# STM32F4_OSD_V12.net
KiCad netlist of a schematic drawn in Altium Designer
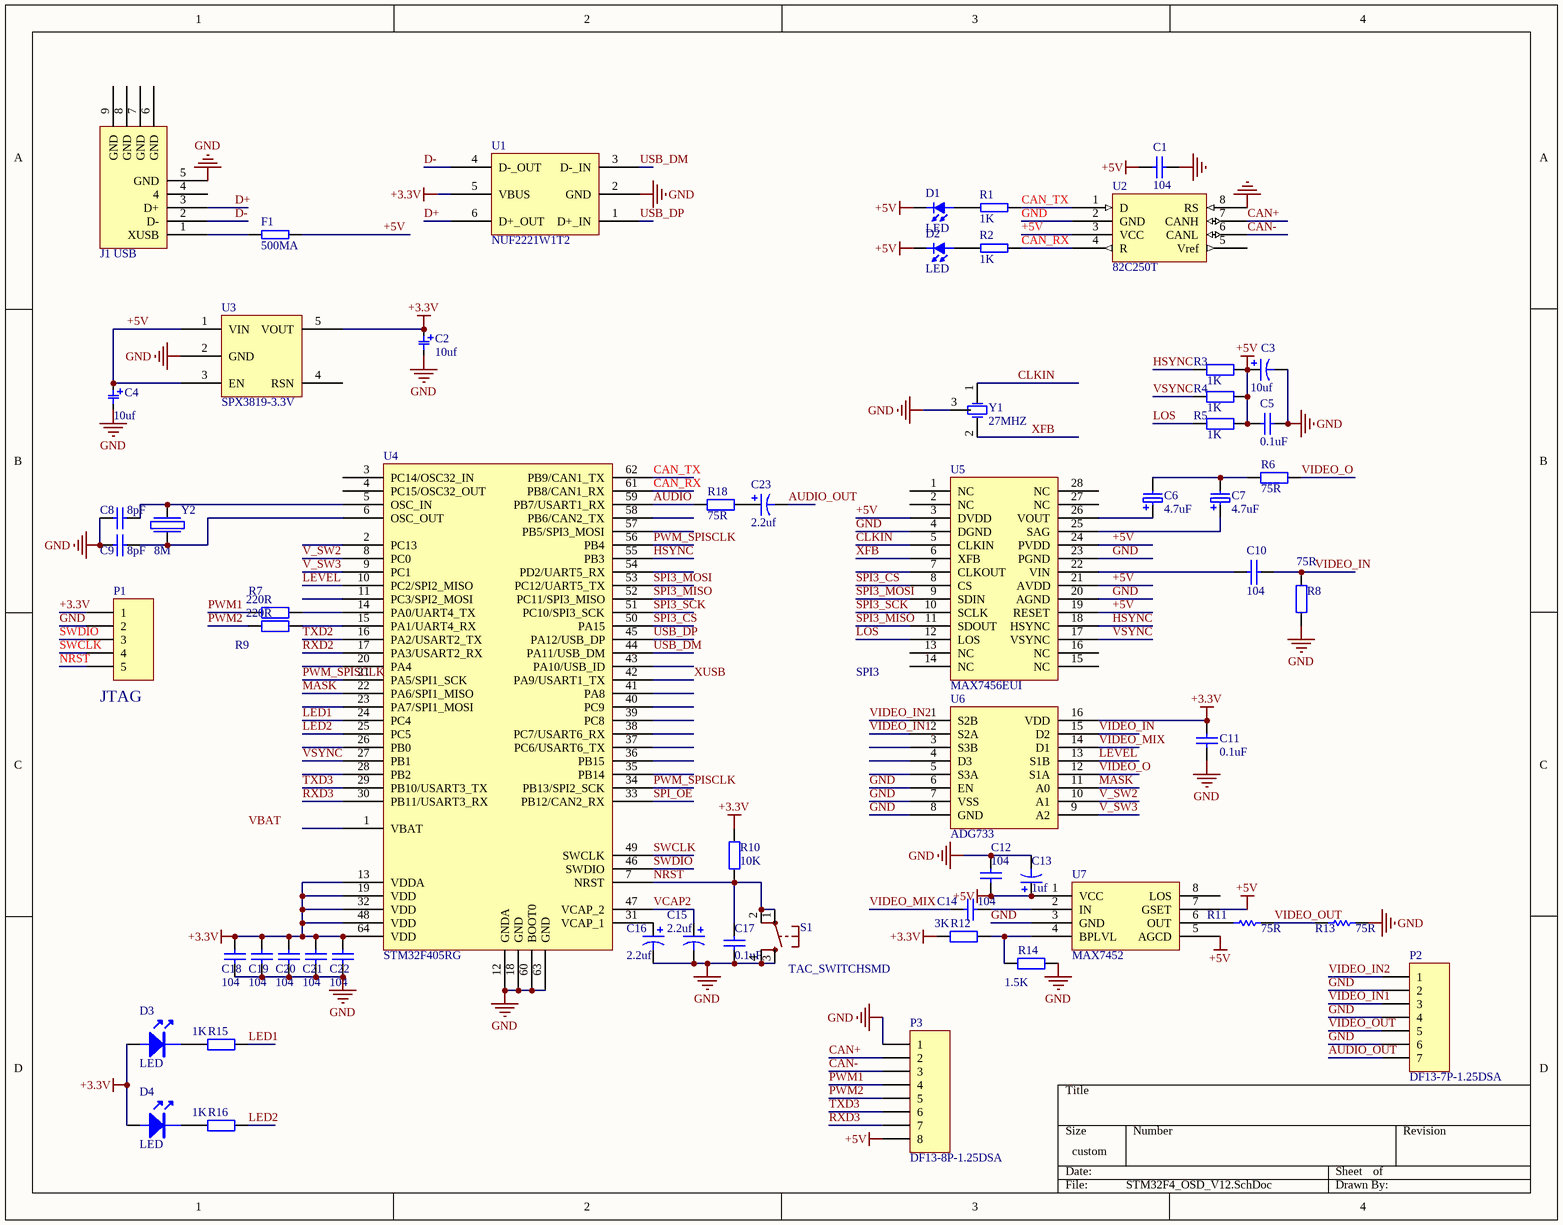
[diagram p0: STM32F4_OSD_V12.SchDoc]

(export (version "E")
  (design (tool "Eeschema 10.0.6"))
  (components
    (comp (ref "C1")
      (value "104")
      (footprint "0603C")
      (description "Capacitor")
      (fields (field (name "PUBLISHER") "Altium Limited"))
      (libsource (lib "*") (part "CAP"))
    )
    (comp (ref "C2") (value "10uf") (footprint "0805") (libsource (lib "电阻电容") (part "ECAP")))
    (comp (ref "C3")
      (value "10uf")
      (footprint "0603C")
      (description "Polarized Capacitor (Radial)")
      (libsource (lib "Miscellaneous Devices") (part "Cap Pol1"))
    )
    (comp (ref "C4") (value "10uf") (footprint "0805") (libsource (lib "电阻电容") (part "ECAP")))
    (comp (ref "C5")
      (value "0.1uF")
      (footprint "0402-CAP")
      (description "Capacitor")
      (fields (field (name "Comment") "Cap") (field (name "PUBLISHER") "Altium Limited"))
      (libsource (lib "Miscellaneous Devices") (part "Cap"))
    )
    (comp (ref "C6")
      (value "4.7uF")
      (footprint "0603C")
      (description "Electrolytic Capacitor 1")
      (libsource (lib "QT_SCH_V2") (part "ELECTRO1"))
    )
    (comp (ref "C7")
      (value "4.7uF")
      (footprint "0603C")
      (description "Electrolytic Capacitor 1")
      (libsource (lib "QT_SCH_V2") (part "ELECTRO1"))
    )
    (comp (ref "C8")
      (value "8pF")
      (footprint "0402-CAP")
      (description "Capacitor")
      (libsource (lib "EMotus Components") (part "CAP0805"))
    )
    (comp (ref "C9")
      (value "8pF")
      (footprint "0402-CAP")
      (description "Capacitor")
      (libsource (lib "EMotus Components") (part "CAP0805"))
    )
    (comp (ref "C10")
      (value "104")
      (footprint "0402-CAP")
      (description "Capacitor")
      (libsource (lib "") (part "CAP_1"))
    )
    (comp (ref "C11")
      (value "0.1uF")
      (footprint "0402-CAP")
      (description "Capacitor")
      (fields (field (name "Comment") "Cap") (field (name "PUBLISHER") "Altium Limited"))
      (libsource (lib "Miscellaneous Devices") (part "Cap"))
    )
    (comp (ref "C12")
      (value "104")
      (footprint "0402-CAP")
      (description "Capacitor")
      (libsource (lib "Miscellaneous Devices") (part "Cap"))
    )
    (comp (ref "C13")
      (value "1uf")
      (footprint "0603C")
      (description "Polarized Capacitor (Radial)")
      (libsource (lib "Miscellaneous Devices") (part "Cap Pol1"))
    )
    (comp (ref "C14")
      (value "104")
      (footprint "0402-CAP")
      (description "Capacitor")
      (libsource (lib "Miscellaneous Devices") (part "Cap"))
    )
    (comp (ref "C15")
      (value "2.2uf")
      (footprint "0603C")
      (description "Polarized Capacitor (Radial)")
      (libsource (lib "Miscellaneous Devices") (part "Cap Pol1"))
    )
    (comp (ref "C16")
      (value "2.2uf")
      (footprint "0603C")
      (description "Polarized Capacitor (Radial)")
      (libsource (lib "Miscellaneous Devices") (part "Cap Pol1"))
    )
    (comp (ref "C17")
      (value "0.1uF")
      (footprint "0402-CAP")
      (description "Capacitor")
      (fields (field (name "Comment") "Cap") (field (name "PUBLISHER") "Altium Limited"))
      (libsource (lib "Miscellaneous Devices") (part "Cap"))
    )
    (comp (ref "C18")
      (value "104")
      (footprint "0402-CAP")
      (description "Capacitor")
      (libsource (lib "Miscellaneous Devices") (part "Cap"))
    )
    (comp (ref "C19")
      (value "104")
      (footprint "0402-CAP")
      (description "Capacitor")
      (libsource (lib "Miscellaneous Devices") (part "Cap"))
    )
    (comp (ref "C20")
      (value "104")
      (footprint "0402-CAP")
      (description "Capacitor")
      (libsource (lib "Miscellaneous Devices") (part "Cap"))
    )
    (comp (ref "C21")
      (value "104")
      (footprint "0402-CAP")
      (description "Capacitor")
      (libsource (lib "Miscellaneous Devices") (part "Cap"))
    )
    (comp (ref "C22")
      (value "104")
      (footprint "0402-CAP")
      (description "Capacitor")
      (libsource (lib "Miscellaneous Devices") (part "Cap"))
    )
    (comp (ref "C23")
      (value "2.2uf")
      (footprint "0603C")
      (description "Polarized Capacitor (Radial)")
      (libsource (lib "Miscellaneous Devices") (part "Cap Pol1"))
    )
    (comp (ref "D1") (value "LED") (footprint "0603-LED") (libsource (lib "原理图库") (part "LED")))
    (comp (ref "D2") (value "LED") (footprint "0603-LED") (libsource (lib "原理图库") (part "LED")))
    (comp (ref "D3") (value "LED") (footprint "0603-LED") (libsource (lib "MySch") (part "LED")))
    (comp (ref "D4") (value "LED") (footprint "0603-LED") (libsource (lib "MySch") (part "LED")))
    (comp (ref "F1") (value "500MA") (footprint "PTC-1206") (libsource (lib "DXP常用原理图库.libsch") (part "RES")))
    (comp (ref "J1")
      (value "USB")
      (footprint "MOLEX_MICRO_USB_AB_BOTTOM_MOUNT")
      (libsource (lib "Schlib1") (part "USB"))
    )
    (comp (ref "P1")
      (value "JTAG")
      (footprint "DF13-5P-1.25DSA")
      (description "Header, 5-Pin")
      (libsource (lib "Miscellaneous Connectors") (part "Header 5"))
    )
    (comp (ref "P2")
      (value "DF13-7P-1.25DSA")
      (footprint "DF13C-7P-1.25V")
      (description "Header, 7-Pin")
      (libsource (lib "Miscellaneous Connectors") (part "Header 7"))
    )
    (comp (ref "P3")
      (value "DF13-8P-1.25DSA")
      (footprint "DF13C-8P-1.25V")
      (description "Header, 8-Pin")
      (libsource (lib "Miscellaneous Connectors") (part "Header 8"))
    )
    (comp (ref "R1") (value "1K") (footprint "0402-RES") (libsource (lib "DXP常用原理图库.libsch") (part "RES")))
    (comp (ref "R2") (value "1K") (footprint "0402-RES") (libsource (lib "DXP常用原理图库.libsch") (part "RES")))
    (comp (ref "R3")
      (value "1K")
      (footprint "0402-RES")
      (description "Resistor")
      (libsource (lib "") (part "Res2_1"))
    )
    (comp (ref "R4")
      (value "1K")
      (footprint "0402-RES")
      (description "Resistor")
      (libsource (lib "") (part "Res2_1"))
    )
    (comp (ref "R5")
      (value "1K")
      (footprint "0402-RES")
      (description "Resistor")
      (libsource (lib "") (part "Res2_1"))
    )
    (comp (ref "R6")
      (value "75R")
      (footprint "0402-RES")
      (description "Resistor")
      (libsource (lib "") (part "Res2_1"))
    )
    (comp (ref "R7")
      (value "220R")
      (footprint "0402-RES")
      (description "Resistor")
      (libsource (lib "") (part "Res2_2"))
    )
    (comp (ref "R8")
      (value "75R")
      (footprint "0402-RES")
      (description "Resistor")
      (libsource (lib "Miscellaneous Devices") (part "Res2"))
    )
    (comp (ref "R9")
      (value "220R")
      (footprint "0402-RES")
      (description "Resistor")
      (libsource (lib "") (part "Res2_2"))
    )
    (comp (ref "R10")
      (value "10K")
      (footprint "0402-RES")
      (description "Resistor")
      (libsource (lib "Miscellaneous Devices") (part "Res2"))
    )
    (comp (ref "R11")
      (value "75R")
      (footprint "0402-RES")
      (description "Resistor")
      (libsource (lib "Miscellaneous Devices") (part "Res1"))
    )
    (comp (ref "R12")
      (value "3K")
      (footprint "0402-RES")
      (description "Resistor")
      (libsource (lib "") (part "Res2_2"))
    )
    (comp (ref "R13")
      (value "75R")
      (footprint "0402-RES")
      (description "Resistor")
      (libsource (lib "Miscellaneous Devices") (part "Res1"))
    )
    (comp (ref "R14")
      (value "1.5K")
      (footprint "0402-RES")
      (description "Resistor")
      (libsource (lib "") (part "Res2_2"))
    )
    (comp (ref "R15")
      (value "1K")
      (footprint "0402-RES")
      (description "Resistor")
      (libsource (lib "") (part "Res2_2"))
    )
    (comp (ref "R16")
      (value "1K")
      (footprint "0402-RES")
      (description "Resistor")
      (libsource (lib "") (part "Res2_2"))
    )
    (comp (ref "R18")
      (value "75R")
      (footprint "0402-RES")
      (description "Resistor")
      (libsource (lib "") (part "Res2_2"))
    )
    (comp (ref "S1")
      (value "TAC_SWITCHSMD")
      (footprint "EVQP7J01K")
      (libsource (lib "DIYdrones3") (part "TAC_SWITCHSMD"))
    )
    (comp (ref "U1")
      (value "NUF2221W1T2")
      (footprint "SOT363")
      (libsource (lib "Schlib1") (part "NUF2221W1T2"))
    )
    (comp (ref "U2") (value "82C250T") (footprint "SO-8N") (libsource (lib "*") (part "SN65HVD230D")))
    (comp (ref "U3") (value "SPX3819-3.3V") (footprint "SOT23-5") (libsource (lib "原理图库") (part "SP6201")))
    (comp (ref "U4")
      (value "STM32F405RG")
      (footprint "LQFP64")
      (libsource (lib "Schlib1") (part "STM32F405RG"))
    )
    (comp (ref "U5") (value "MAX7456EUI") (footprint "SSOP-28") (libsource (lib "Schlib1") (part "MAX7456")))
    (comp (ref "U6") (value "ADG733") (footprint "TSOP16") (libsource (lib "Schlib1") (part "ADG733")))
    (comp (ref "U7") (value "MAX7452") (footprint "SOIC-SN8_N") (libsource (lib "Schlib1") (part "MAX7452")))
    (comp (ref "Y1") (value "27MHZ") (footprint "27MHZ") (libsource (lib "晶振滤波器") (part "晶振3脚")))
    (comp (ref "Y2")
      (value "8M")
      (footprint "OSCILLATOR-3.2X2.5")
      (description "7B-8.000MAAJ-T")
      (libsource (lib "passive") (part "ZQ_KX12B"))
    )
  )
  (nets
    (net (code "1") (name "+3.3V") (class "Default")
      (node (ref "C11") (pin "2") (pinfunction "2_2") (pintype "passive"))
      (node (ref "C18") (pin "2") (pinfunction "2_2") (pintype "passive"))
      (node (ref "C19") (pin "2") (pinfunction "2_2") (pintype "passive"))
      (node (ref "C2") (pin "2") (pintype "passive"))
      (node (ref "C20") (pin "2") (pinfunction "2_2") (pintype "passive"))
      (node (ref "C21") (pin "2") (pinfunction "2_2") (pintype "passive"))
      (node (ref "C22") (pin "2") (pinfunction "2_2") (pintype "passive"))
      (node (ref "D3") (pin "1") (pinfunction "1_1") (pintype "passive"))
      (node (ref "D4") (pin "1") (pinfunction "1_1") (pintype "passive"))
      (node (ref "P1") (pin "1") (pinfunction "1_1") (pintype "passive"))
      (node (ref "R10") (pin "2") (pinfunction "2_2") (pintype "passive"))
      (node (ref "R12") (pin "2") (pinfunction "2_2") (pintype "passive"))
      (node (ref "U1") (pin "5") (pinfunction "VBUS_5") (pintype "passive"))
      (node (ref "U3") (pin "5") (pinfunction "VOUT_5") (pintype "passive"))
      (node (ref "U4") (pin "13") (pinfunction "VDDA_13") (pintype "passive"))
      (node (ref "U4") (pin "19") (pinfunction "VDD_19") (pintype "passive"))
      (node (ref "U4") (pin "32") (pinfunction "VDD_32") (pintype "passive"))
      (node (ref "U4") (pin "48") (pinfunction "VDD_48") (pintype "passive"))
      (node (ref "U4") (pin "64") (pinfunction "VDD_64") (pintype "passive"))
      (node (ref "U6") (pin "16") (pinfunction "VDD_16") (pintype "passive"))
    )
    (net (code "2") (name "+5V") (class "Default")
      (node (ref "C1") (pin "2") (pinfunction "2_2") (pintype "passive"))
      (node (ref "C12") (pin "1") (pinfunction "1_1") (pintype "passive"))
      (node (ref "C13") (pin "1") (pinfunction "1_1") (pintype "passive"))
      (node (ref "C3") (pin "1") (pinfunction "1_1") (pintype "passive"))
      (node (ref "C4") (pin "2") (pintype "passive"))
      (node (ref "C5") (pin "1") (pinfunction "1_1") (pintype "passive"))
      (node (ref "D1") (pin "2") (pinfunction "2_2") (pintype "passive"))
      (node (ref "D2") (pin "2") (pinfunction "2_2") (pintype "passive"))
      (node (ref "F1") (pin "1") (pinfunction "1_1") (pintype "passive"))
      (node (ref "P3") (pin "8") (pinfunction "8_8") (pintype "passive"))
      (node (ref "R3") (pin "2") (pinfunction "2_2") (pintype "passive"))
      (node (ref "R4") (pin "2") (pinfunction "2_2") (pintype "passive"))
      (node (ref "R5") (pin "2") (pinfunction "2_2") (pintype "passive"))
      (node (ref "U2") (pin "3") (pinfunction "VCC_3") (pintype "power_in"))
      (node (ref "U3") (pin "1") (pinfunction "VIN_1") (pintype "passive"))
      (node (ref "U3") (pin "3") (pinfunction "EN_3") (pintype "passive"))
      (node (ref "U5") (pin "19") (pinfunction "RESET_19") (pintype "passive"))
      (node (ref "U5") (pin "21") (pinfunction "AVDD_21") (pintype "passive"))
      (node (ref "U5") (pin "24") (pinfunction "PVDD_24") (pintype "passive"))
      (node (ref "U5") (pin "3") (pinfunction "DVDD_3") (pintype "passive"))
      (node (ref "U7") (pin "1") (pinfunction "VCC_1") (pintype "passive"))
      (node (ref "U7") (pin "5") (pinfunction "AGCD_5") (pintype "passive"))
      (node (ref "U7") (pin "7") (pinfunction "GSET_7") (pintype "passive"))
    )
    (net (code "3") (name "/AUDIO") (class "Default")
      (node (ref "R18") (pin "2") (pinfunction "2_2") (pintype "passive"))
      (node (ref "U4") (pin "59") (pinfunction "PB7/USART1_RX_59") (pintype "passive"))
    )
    (net (code "4") (name "/AUDIO_OUT") (class "Default")
      (node (ref "C23") (pin "2") (pinfunction "2_2") (pintype "passive"))
      (node (ref "P2") (pin "7") (pinfunction "7_7") (pintype "passive"))
    )
    (net (code "5") (name "/CAN+") (class "Default")
      (node (ref "P3") (pin "2") (pinfunction "2_2") (pintype "passive"))
      (node (ref "U2") (pin "7") (pinfunction "CANH_7") (pintype "bidirectional"))
    )
    (net (code "6") (name "/CAN-") (class "Default")
      (node (ref "P3") (pin "3") (pinfunction "3_3") (pintype "passive"))
      (node (ref "U2") (pin "6") (pinfunction "CANL_6") (pintype "bidirectional"))
    )
    (net (code "7") (name "/CAN_RX") (class "Default")
      (node (ref "R2") (pin "2") (pinfunction "2_2") (pintype "passive"))
      (node (ref "U2") (pin "4") (pinfunction "R_4") (pintype "output"))
      (node (ref "U4") (pin "61") (pinfunction "PB8/CAN1_RX_61") (pintype "passive"))
    )
    (net (code "8") (name "/CAN_TX") (class "Default")
      (node (ref "R1") (pin "2") (pinfunction "2_2") (pintype "passive"))
      (node (ref "U2") (pin "1") (pinfunction "D_1") (pintype "input"))
      (node (ref "U4") (pin "62") (pinfunction "PB9/CAN1_TX_62") (pintype "passive"))
    )
    (net (code "9") (name "/CLKIN") (class "Default")
      (node (ref "U5") (pin "5") (pinfunction "CLKIN_5") (pintype "passive"))
      (node (ref "Y1") (pin "1") (pinfunction "1_1") (pintype "passive"))
    )
    (net (code "10") (name "/D+") (class "Default")
      (node (ref "J1") (pin "3") (pinfunction "D+_3") (pintype "passive"))
      (node (ref "U1") (pin "6") (pinfunction "D+_OUT_6") (pintype "passive"))
    )
    (net (code "11") (name "/D-") (class "Default")
      (node (ref "J1") (pin "2") (pinfunction "D-_2") (pintype "passive"))
      (node (ref "U1") (pin "4") (pinfunction "D-_OUT_4") (pintype "passive"))
    )
    (net (code "12") (name "/HSYNC") (class "Default")
      (node (ref "R3") (pin "1") (pinfunction "1_1") (pintype "passive"))
      (node (ref "U4") (pin "55") (pinfunction "PB3_55") (pintype "passive"))
      (node (ref "U5") (pin "18") (pinfunction "HSYNC_18") (pintype "passive"))
    )
    (net (code "13") (name "/LED1") (class "Default")
      (node (ref "R15") (pin "1") (pinfunction "1_1") (pintype "passive"))
      (node (ref "U4") (pin "24") (pinfunction "PC4_24") (pintype "passive"))
    )
    (net (code "14") (name "/LED2") (class "Default")
      (node (ref "R16") (pin "1") (pinfunction "1_1") (pintype "passive"))
      (node (ref "U4") (pin "25") (pinfunction "PC5_25") (pintype "passive"))
    )
    (net (code "15") (name "/LEVEL") (class "Default")
      (node (ref "U4") (pin "10") (pinfunction "PC2/SPI2_MISO_10") (pintype "passive"))
      (node (ref "U6") (pin "13") (pinfunction "S1B_13") (pintype "passive"))
    )
    (net (code "16") (name "/LOS") (class "Default")
      (node (ref "R5") (pin "1") (pinfunction "1_1") (pintype "passive"))
      (node (ref "U5") (pin "12") (pinfunction "LOS_12") (pintype "passive"))
    )
    (net (code "17") (name "/MASK") (class "Default")
      (node (ref "U4") (pin "22") (pinfunction "PA6/SPI1_MISO_22") (pintype "passive"))
      (node (ref "U6") (pin "11") (pinfunction "A0_11") (pintype "passive"))
    )
    (net (code "18") (name "/NRST") (class "Default")
      (node (ref "C17") (pin "2") (pinfunction "2_2") (pintype "passive"))
      (node (ref "P1") (pin "5") (pinfunction "5_5") (pintype "passive"))
      (node (ref "R10") (pin "1") (pinfunction "1_1") (pintype "passive"))
      (node (ref "S1") (pin "1") (pinfunction "1_1") (pintype "passive"))
      (node (ref "S1") (pin "2") (pinfunction "2_2") (pintype "passive"))
      (node (ref "U4") (pin "7") (pinfunction "NRST_7") (pintype "passive"))
    )
    (net (code "19") (name "/PWM1") (class "Default")
      (node (ref "P3") (pin "4") (pinfunction "4_4") (pintype "passive"))
      (node (ref "R7") (pin "2") (pinfunction "2_2") (pintype "passive"))
    )
    (net (code "20") (name "/PWM2") (class "Default")
      (node (ref "P3") (pin "5") (pinfunction "5_5") (pintype "passive"))
      (node (ref "R9") (pin "2") (pinfunction "2_2") (pintype "passive"))
    )
    (net (code "21") (name "/PWM_SPISCLK") (class "Default")
      (node (ref "U4") (pin "21") (pinfunction "PA5/SPI1_SCK_21") (pintype "passive"))
      (node (ref "U4") (pin "34") (pinfunction "PB13/SPI2_SCK_34") (pintype "passive"))
      (node (ref "U4") (pin "56") (pinfunction "PB4_56") (pintype "passive"))
    )
    (net (code "22") (name "/RXD2") (class "Default")
      (node (ref "U4") (pin "17") (pinfunction "PA3/USART2_RX_17") (pintype "passive"))
    )
    (net (code "23") (name "/RXD3") (class "Default")
      (node (ref "P3") (pin "7") (pinfunction "7_7") (pintype "passive"))
      (node (ref "U4") (pin "30") (pinfunction "PB11/USART3_RX_30") (pintype "passive"))
    )
    (net (code "24") (name "/SPI3_CS") (class "Default")
      (node (ref "U4") (pin "50") (pinfunction "PA15_50") (pintype "passive"))
      (node (ref "U5") (pin "8") (pinfunction "CS_8") (pintype "passive"))
    )
    (net (code "25") (name "/SPI3_MISO") (class "Default")
      (node (ref "U4") (pin "52") (pinfunction "PC11/SPI3_MISO_52") (pintype "passive"))
      (node (ref "U5") (pin "11") (pinfunction "SDOUT_11") (pintype "passive"))
    )
    (net (code "26") (name "/SPI3_MOSI") (class "Default")
      (node (ref "U4") (pin "53") (pinfunction "PC12/UART5_TX_53") (pintype "passive"))
      (node (ref "U5") (pin "9") (pinfunction "SDIN_9") (pintype "passive"))
    )
    (net (code "27") (name "/SPI3_SCK") (class "Default")
      (node (ref "U4") (pin "51") (pinfunction "PC10/SPI3_SCK_51") (pintype "passive"))
      (node (ref "U5") (pin "10") (pinfunction "SCLK_10") (pintype "passive"))
    )
    (net (code "28") (name "/SPI_OE") (class "Default")
      (node (ref "U4") (pin "33") (pinfunction "PB12/CAN2_RX_33") (pintype "passive"))
    )
    (net (code "29") (name "/SWCLK") (class "Default")
      (node (ref "P1") (pin "4") (pinfunction "4_4") (pintype "passive"))
      (node (ref "U4") (pin "49") (pinfunction "SWCLK_49") (pintype "passive"))
    )
    (net (code "30") (name "/SWDIO") (class "Default")
      (node (ref "P1") (pin "3") (pinfunction "3_3") (pintype "passive"))
      (node (ref "U4") (pin "46") (pinfunction "SWDIO_46") (pintype "passive"))
    )
    (net (code "31") (name "/TXD2") (class "Default")
      (node (ref "U4") (pin "16") (pinfunction "PA2/USART2_TX_16") (pintype "passive"))
    )
    (net (code "32") (name "/TXD3") (class "Default")
      (node (ref "P3") (pin "6") (pinfunction "6_6") (pintype "passive"))
      (node (ref "U4") (pin "29") (pinfunction "PB10/USART3_TX_29") (pintype "passive"))
    )
    (net (code "33") (name "/USB_DM") (class "Default")
      (node (ref "U1") (pin "3") (pinfunction "D-_IN_3") (pintype "passive"))
      (node (ref "U4") (pin "44") (pinfunction "PA11/USB_DM_44") (pintype "passive"))
    )
    (net (code "34") (name "/USB_DP") (class "Default")
      (node (ref "U1") (pin "1") (pinfunction "D+_IN_1") (pintype "passive"))
      (node (ref "U4") (pin "45") (pinfunction "PA12/USB_DP_45") (pintype "passive"))
    )
    (net (code "36") (name "/VCAP2") (class "Default")
      (node (ref "C15") (pin "1") (pinfunction "1_1") (pintype "passive"))
      (node (ref "U4") (pin "47") (pinfunction "VCAP_2_47") (pintype "passive"))
    )
    (net (code "37") (name "/VIDEO_IN") (class "Default")
      (node (ref "C10") (pin "2") (pinfunction "2_2") (pintype "passive"))
      (node (ref "R8") (pin "2") (pinfunction "2_2") (pintype "passive"))
      (node (ref "U6") (pin "15") (pinfunction "D2_15") (pintype "passive"))
    )
    (net (code "38") (name "/VIDEO_IN1") (class "Default")
      (node (ref "P2") (pin "3") (pinfunction "3_3") (pintype "passive"))
      (node (ref "U6") (pin "2") (pinfunction "S2A_2") (pintype "passive"))
    )
    (net (code "39") (name "/VIDEO_IN2") (class "Default")
      (node (ref "P2") (pin "1") (pinfunction "1_1") (pintype "passive"))
      (node (ref "U6") (pin "1") (pinfunction "S2B_1") (pintype "passive"))
    )
    (net (code "40") (name "/VIDEO_MIX") (class "Default")
      (node (ref "C14") (pin "1") (pinfunction "1_1") (pintype "passive"))
      (node (ref "U6") (pin "14") (pinfunction "D1_14") (pintype "passive"))
    )
    (net (code "41") (name "/VIDEO_O") (class "Default")
      (node (ref "R6") (pin "2") (pinfunction "2_2") (pintype "passive"))
      (node (ref "U6") (pin "12") (pinfunction "S1A_12") (pintype "passive"))
    )
    (net (code "42") (name "/VIDEO_OUT") (class "Default")
      (node (ref "P2") (pin "5") (pinfunction "5_5") (pintype "passive"))
      (node (ref "R11") (pin "1") (pinfunction "1_1") (pintype "passive"))
      (node (ref "R13") (pin "2") (pinfunction "2_2") (pintype "passive"))
    )
    (net (code "43") (name "/VSYNC") (class "Default")
      (node (ref "R4") (pin "1") (pinfunction "1_1") (pintype "passive"))
      (node (ref "U4") (pin "27") (pinfunction "PB1_27") (pintype "passive"))
      (node (ref "U5") (pin "17") (pinfunction "VSYNC_17") (pintype "passive"))
    )
    (net (code "44") (name "/V_SW2") (class "Default")
      (node (ref "U4") (pin "8") (pinfunction "PC0_8") (pintype "passive"))
      (node (ref "U6") (pin "10") (pinfunction "A1_10") (pintype "passive"))
    )
    (net (code "45") (name "/V_SW3") (class "Default")
      (node (ref "U4") (pin "9") (pinfunction "PC1_9") (pintype "passive"))
      (node (ref "U6") (pin "9") (pinfunction "A2_9") (pintype "passive"))
    )
    (net (code "46") (name "/XFB") (class "Default")
      (node (ref "U5") (pin "6") (pinfunction "XFB_6") (pintype "passive"))
      (node (ref "Y1") (pin "2") (pinfunction "2_2") (pintype "passive"))
    )
    (net (code "47") (name "/XUSB") (class "Default")
      (node (ref "U4") (pin "42") (pinfunction "PA9/USART1_TX_42") (pintype "passive"))
    )
    (net (code "48") (name "GND") (class "Default")
      (node (ref "C1") (pin "1") (pinfunction "1_1") (pintype "passive"))
      (node (ref "C11") (pin "1") (pinfunction "1_1") (pintype "passive"))
      (node (ref "C12") (pin "2") (pinfunction "2_2") (pintype "passive"))
      (node (ref "C13") (pin "2") (pinfunction "2_2") (pintype "passive"))
      (node (ref "C15") (pin "2") (pinfunction "2_2") (pintype "passive"))
      (node (ref "C16") (pin "2") (pinfunction "2_2") (pintype "passive"))
      (node (ref "C17") (pin "1") (pinfunction "1_1") (pintype "passive"))
      (node (ref "C18") (pin "1") (pinfunction "1_1") (pintype "passive"))
      (node (ref "C19") (pin "1") (pinfunction "1_1") (pintype "passive"))
      (node (ref "C2") (pin "1") (pintype "passive"))
      (node (ref "C20") (pin "1") (pinfunction "1_1") (pintype "passive"))
      (node (ref "C21") (pin "1") (pinfunction "1_1") (pintype "passive"))
      (node (ref "C22") (pin "1") (pinfunction "1_1") (pintype "passive"))
      (node (ref "C3") (pin "2") (pinfunction "2_2") (pintype "passive"))
      (node (ref "C4") (pin "1") (pintype "passive"))
      (node (ref "C5") (pin "2") (pinfunction "2_2") (pintype "passive"))
      (node (ref "C8") (pin "2") (pinfunction "2_2") (pintype "passive"))
      (node (ref "C9") (pin "2") (pinfunction "2_2") (pintype "passive"))
      (node (ref "J1") (pin "5") (pinfunction "GND_5") (pintype "passive"))
      (node (ref "P1") (pin "2") (pinfunction "2_2") (pintype "passive"))
      (node (ref "P2") (pin "2") (pinfunction "2_2") (pintype "passive"))
      (node (ref "P2") (pin "4") (pinfunction "4_4") (pintype "passive"))
      (node (ref "P2") (pin "6") (pinfunction "6_6") (pintype "passive"))
      (node (ref "P3") (pin "1") (pinfunction "1_1") (pintype "passive"))
      (node (ref "R13") (pin "1") (pinfunction "1_1") (pintype "passive"))
      (node (ref "R14") (pin "1") (pinfunction "1_1") (pintype "passive"))
      (node (ref "R8") (pin "1") (pinfunction "1_1") (pintype "passive"))
      (node (ref "S1") (pin "3") (pinfunction "3_3") (pintype "passive"))
      (node (ref "S1") (pin "4") (pinfunction "4_4") (pintype "passive"))
      (node (ref "U1") (pin "2") (pinfunction "GND_2") (pintype "passive"))
      (node (ref "U2") (pin "2") (pinfunction "GND_2") (pintype "power_in"))
      (node (ref "U2") (pin "8") (pinfunction "RS_8") (pintype "input"))
      (node (ref "U3") (pin "2") (pinfunction "GND_2") (pintype "passive"))
      (node (ref "U4") (pin "12") (pinfunction "GNDA_12") (pintype "passive"))
      (node (ref "U4") (pin "18") (pinfunction "GND_18") (pintype "passive"))
      (node (ref "U4") (pin "60") (pinfunction "BOOT0_60") (pintype "passive"))
      (node (ref "U4") (pin "63") (pinfunction "GND_63") (pintype "passive"))
      (node (ref "U5") (pin "20") (pinfunction "AGND_20") (pintype "passive"))
      (node (ref "U5") (pin "23") (pinfunction "PGND_23") (pintype "passive"))
      (node (ref "U5") (pin "4") (pinfunction "DGND_4") (pintype "passive"))
      (node (ref "U6") (pin "6") (pinfunction "EN_6") (pintype "passive"))
      (node (ref "U6") (pin "7") (pinfunction "VSS_7") (pintype "passive"))
      (node (ref "U6") (pin "8") (pinfunction "GND_8") (pintype "passive"))
      (node (ref "U7") (pin "3") (pinfunction "GND_3") (pintype "passive"))
      (node (ref "Y1") (pin "3") (pinfunction "3_3") (pintype "passive"))
    )
    (net (code "49") (name "Net-(C6-Pad2)") (class "Default")
      (node (ref "C6") (pin "2") (pinfunction "2_2") (pintype "passive"))
      (node (ref "C7") (pin "2") (pinfunction "2_2") (pintype "passive"))
      (node (ref "R6") (pin "1") (pinfunction "1_1") (pintype "passive"))
    )
    (net (code "50") (name "Net-(C23-Pad1)") (class "Default")
      (node (ref "C23") (pin "1") (pinfunction "1_1") (pintype "passive"))
      (node (ref "R18") (pin "1") (pinfunction "1_1") (pintype "passive"))
    )
    (net (code "51") (name "Net-(D1-Pad1)") (class "Default")
      (node (ref "D1") (pin "1") (pinfunction "1_1") (pintype "passive"))
      (node (ref "R1") (pin "1") (pinfunction "1_1") (pintype "passive"))
    )
    (net (code "52") (name "Net-(D2-Pad1)") (class "Default")
      (node (ref "D2") (pin "1") (pinfunction "1_1") (pintype "passive"))
      (node (ref "R2") (pin "1") (pinfunction "1_1") (pintype "passive"))
    )
    (net (code "53") (name "Net-(D3-Pad2)") (class "Default")
      (node (ref "D3") (pin "2") (pinfunction "2_2") (pintype "passive"))
      (node (ref "R15") (pin "2") (pinfunction "2_2") (pintype "passive"))
    )
    (net (code "54") (name "Net-(D4-Pad2)") (class "Default")
      (node (ref "D4") (pin "2") (pinfunction "2_2") (pintype "passive"))
      (node (ref "R16") (pin "2") (pinfunction "2_2") (pintype "passive"))
    )
    (net (code "55") (name "Net-(J1-XUSB)") (class "Default")
      (node (ref "F1") (pin "2") (pinfunction "2_2") (pintype "passive"))
      (node (ref "J1") (pin "1") (pinfunction "XUSB_1") (pintype "passive"))
    )
    (net (code "56") (name "Net-(U4-OSC_IN)") (class "Default")
      (node (ref "C8") (pin "1") (pinfunction "1_1") (pintype "passive"))
      (node (ref "U4") (pin "5") (pinfunction "OSC_IN_5") (pintype "passive"))
      (node (ref "Y2") (pin "1") (pinfunction "1_1") (pintype "passive"))
    )
    (net (code "57") (name "Net-(U4-OSC_OUT)") (class "Default")
      (node (ref "C9") (pin "1") (pinfunction "1_1") (pintype "passive"))
      (node (ref "U4") (pin "6") (pinfunction "OSC_OUT_6") (pintype "passive"))
      (node (ref "Y2") (pin "2") (pinfunction "2_2") (pintype "passive"))
    )
    (net (code "58") (name "Net-(U4-PA0{slash}UART4_TX)") (class "Default")
      (node (ref "R7") (pin "1") (pinfunction "1_1") (pintype "passive"))
      (node (ref "U4") (pin "14") (pinfunction "PA0/UART4_TX_14") (pintype "passive"))
    )
    (net (code "59") (name "Net-(U4-PA1{slash}UART4_RX)") (class "Default")
      (node (ref "R9") (pin "1") (pinfunction "1_1") (pintype "passive"))
      (node (ref "U4") (pin "15") (pinfunction "PA1/UART4_RX_15") (pintype "passive"))
    )
    (net (code "60") (name "Net-(U4-VCAP_1)") (class "Default")
      (node (ref "C16") (pin "1") (pinfunction "1_1") (pintype "passive"))
      (node (ref "U4") (pin "31") (pinfunction "VCAP_1_31") (pintype "passive"))
    )
    (net (code "61") (name "Net-(U5-SAG)") (class "Default")
      (node (ref "C7") (pin "1") (pinfunction "1_1") (pintype "passive"))
      (node (ref "U5") (pin "25") (pinfunction "SAG_25") (pintype "passive"))
    )
    (net (code "62") (name "Net-(U5-VIN)") (class "Default")
      (node (ref "C10") (pin "1") (pinfunction "1_1") (pintype "passive"))
      (node (ref "U5") (pin "22") (pinfunction "VIN_22") (pintype "passive"))
    )
    (net (code "63") (name "Net-(U5-VOUT)") (class "Default")
      (node (ref "C6") (pin "1") (pinfunction "1_1") (pintype "passive"))
      (node (ref "U5") (pin "26") (pinfunction "VOUT_26") (pintype "passive"))
    )
    (net (code "64") (name "Net-(U7-BPLVL)") (class "Default")
      (node (ref "R12") (pin "1") (pinfunction "1_1") (pintype "passive"))
      (node (ref "R14") (pin "2") (pinfunction "2_2") (pintype "passive"))
      (node (ref "U7") (pin "4") (pinfunction "BPLVL_4") (pintype "passive"))
    )
    (net (code "65") (name "Net-(U7-IN)") (class "Default")
      (node (ref "C14") (pin "2") (pinfunction "2_2") (pintype "passive"))
      (node (ref "U7") (pin "2") (pinfunction "IN_2") (pintype "passive"))
    )
    (net (code "66") (name "Net-(U7-OUT)") (class "Default")
      (node (ref "R11") (pin "2") (pinfunction "2_2") (pintype "passive"))
      (node (ref "U7") (pin "6") (pinfunction "OUT_6") (pintype "passive"))
    )
    (net (code "67") (name "unconnected-(J1-GND-Pad6)") (class "Default")
      (node (ref "J1") (pin "6") (pinfunction "GND_6") (pintype "passive"))
    )
    (net (code "68") (name "unconnected-(J1-GND-Pad7)") (class "Default")
      (node (ref "J1") (pin "7") (pinfunction "GND_7") (pintype "passive"))
    )
    (net (code "69") (name "unconnected-(J1-GND-Pad8)") (class "Default")
      (node (ref "J1") (pin "8") (pinfunction "GND_8") (pintype "passive"))
    )
    (net (code "70") (name "unconnected-(J1-GND-Pad9)") (class "Default")
      (node (ref "J1") (pin "9") (pinfunction "GND_9") (pintype "passive"))
    )
    (net (code "71") (name "unconnected-(J1-Pad4)") (class "Default")
      (node (ref "J1") (pin "4") (pinfunction "4_4") (pintype "passive"))
    )
    (net (code "72") (name "unconnected-(U2-Vref-Pad5)") (class "Default")
      (node (ref "U2") (pin "5") (pinfunction "Vref_5") (pintype "output"))
    )
    (net (code "73") (name "unconnected-(U3-RSN-Pad4)") (class "Default")
      (node (ref "U3") (pin "4") (pinfunction "RSN_4") (pintype "passive"))
    )
    (net (code "74") (name "unconnected-(U4-PA4-Pad20)") (class "Default")
      (node (ref "U4") (pin "20") (pinfunction "PA4_20") (pintype "passive"))
    )
    (net (code "75") (name "unconnected-(U4-PA7{slash}SPI1_MOSI-Pad23)") (class "Default")
      (node (ref "U4") (pin "23") (pinfunction "PA7/SPI1_MOSI_23") (pintype "passive"))
    )
    (net (code "76") (name "unconnected-(U4-PA8-Pad41)") (class "Default")
      (node (ref "U4") (pin "41") (pinfunction "PA8_41") (pintype "passive"))
    )
    (net (code "77") (name "unconnected-(U4-PA10{slash}USB_ID-Pad43)") (class "Default")
      (node (ref "U4") (pin "43") (pinfunction "PA10/USB_ID_43") (pintype "passive"))
    )
    (net (code "78") (name "unconnected-(U4-PB0-Pad26)") (class "Default")
      (node (ref "U4") (pin "26") (pinfunction "PB0_26") (pintype "passive"))
    )
    (net (code "79") (name "unconnected-(U4-PB2-Pad28)") (class "Default")
      (node (ref "U4") (pin "28") (pinfunction "PB2_28") (pintype "passive"))
    )
    (net (code "80") (name "unconnected-(U4-PB5{slash}SPI3_MOSI-Pad57)") (class "Default")
      (node (ref "U4") (pin "57") (pinfunction "PB5/SPI3_MOSI_57") (pintype "passive"))
    )
    (net (code "81") (name "unconnected-(U4-PB6{slash}CAN2_TX-Pad58)") (class "Default")
      (node (ref "U4") (pin "58") (pinfunction "PB6/CAN2_TX_58") (pintype "passive"))
    )
    (net (code "82") (name "unconnected-(U4-PB14-Pad35)") (class "Default")
      (node (ref "U4") (pin "35") (pinfunction "PB14_35") (pintype "passive"))
    )
    (net (code "83") (name "unconnected-(U4-PB15-Pad36)") (class "Default")
      (node (ref "U4") (pin "36") (pinfunction "PB15_36") (pintype "passive"))
    )
    (net (code "84") (name "unconnected-(U4-PC3{slash}SPI2_MOSI-Pad11)") (class "Default")
      (node (ref "U4") (pin "11") (pinfunction "PC3/SPI2_MOSI_11") (pintype "passive"))
    )
    (net (code "85") (name "unconnected-(U4-PC6{slash}USART6_TX-Pad37)") (class "Default")
      (node (ref "U4") (pin "37") (pinfunction "PC6/USART6_TX_37") (pintype "passive"))
    )
    (net (code "86") (name "unconnected-(U4-PC7{slash}USART6_RX-Pad38)") (class "Default")
      (node (ref "U4") (pin "38") (pinfunction "PC7/USART6_RX_38") (pintype "passive"))
    )
    (net (code "87") (name "unconnected-(U4-PC8-Pad39)") (class "Default")
      (node (ref "U4") (pin "39") (pinfunction "PC8_39") (pintype "passive"))
    )
    (net (code "88") (name "unconnected-(U4-PC9-Pad40)") (class "Default")
      (node (ref "U4") (pin "40") (pinfunction "PC9_40") (pintype "passive"))
    )
    (net (code "89") (name "unconnected-(U4-PC13-Pad2)") (class "Default")
      (node (ref "U4") (pin "2") (pinfunction "PC13_2") (pintype "passive"))
    )
    (net (code "90") (name "unconnected-(U4-PC14{slash}OSC32_IN-Pad3)") (class "Default")
      (node (ref "U4") (pin "3") (pinfunction "PC14/OSC32_IN_3") (pintype "passive"))
    )
    (net (code "91") (name "unconnected-(U4-PC15{slash}OSC32_OUT-Pad4)") (class "Default")
      (node (ref "U4") (pin "4") (pinfunction "PC15/OSC32_OUT_4") (pintype "passive"))
    )
    (net (code "92") (name "unconnected-(U4-PD2{slash}UART5_RX-Pad54)") (class "Default")
      (node (ref "U4") (pin "54") (pinfunction "PD2/UART5_RX_54") (pintype "passive"))
    )
    (net (code "93") (name "unconnected-(U4-VBAT-Pad1)") (class "Default")
      (node (ref "U4") (pin "1") (pinfunction "VBAT_1") (pintype "passive"))
    )
    (net (code "94") (name "unconnected-(U5-CLKOUT-Pad7)") (class "Default")
      (node (ref "U5") (pin "7") (pinfunction "CLKOUT_7") (pintype "passive"))
    )
    (net (code "95") (name "unconnected-(U5-NC-Pad1)") (class "Default")
      (node (ref "U5") (pin "1") (pinfunction "NC_1") (pintype "passive"))
    )
    (net (code "96") (name "unconnected-(U5-NC-Pad2)") (class "Default")
      (node (ref "U5") (pin "2") (pinfunction "NC_2") (pintype "passive"))
    )
    (net (code "97") (name "unconnected-(U5-NC-Pad13)") (class "Default")
      (node (ref "U5") (pin "13") (pinfunction "NC_13") (pintype "passive"))
    )
    (net (code "98") (name "unconnected-(U5-NC-Pad14)") (class "Default")
      (node (ref "U5") (pin "14") (pinfunction "NC_14") (pintype "passive"))
    )
    (net (code "99") (name "unconnected-(U5-NC-Pad15)") (class "Default")
      (node (ref "U5") (pin "15") (pinfunction "NC_15") (pintype "passive"))
    )
    (net (code "100") (name "unconnected-(U5-NC-Pad16)") (class "Default")
      (node (ref "U5") (pin "16") (pinfunction "NC_16") (pintype "passive"))
    )
    (net (code "101") (name "unconnected-(U5-NC-Pad27)") (class "Default")
      (node (ref "U5") (pin "27") (pinfunction "NC_27") (pintype "passive"))
    )
    (net (code "102") (name "unconnected-(U5-NC-Pad28)") (class "Default")
      (node (ref "U5") (pin "28") (pinfunction "NC_28") (pintype "passive"))
    )
    (net (code "103") (name "unconnected-(U6-D3-Pad4)") (class "Default")
      (node (ref "U6") (pin "4") (pinfunction "D3_4") (pintype "passive"))
    )
    (net (code "104") (name "unconnected-(U6-S3A-Pad5)") (class "Default")
      (node (ref "U6") (pin "5") (pinfunction "S3A_5") (pintype "passive"))
    )
    (net (code "105") (name "unconnected-(U6-S3B-Pad3)") (class "Default")
      (node (ref "U6") (pin "3") (pinfunction "S3B_3") (pintype "passive"))
    )
    (net (code "106") (name "unconnected-(U7-LOS-Pad8)") (class "Default")
      (node (ref "U7") (pin "8") (pinfunction "LOS_8") (pintype "passive"))
    )
  )
)
